# nixie_test_v3.net
KiCad netlist of a schematic drawn in EAGLE
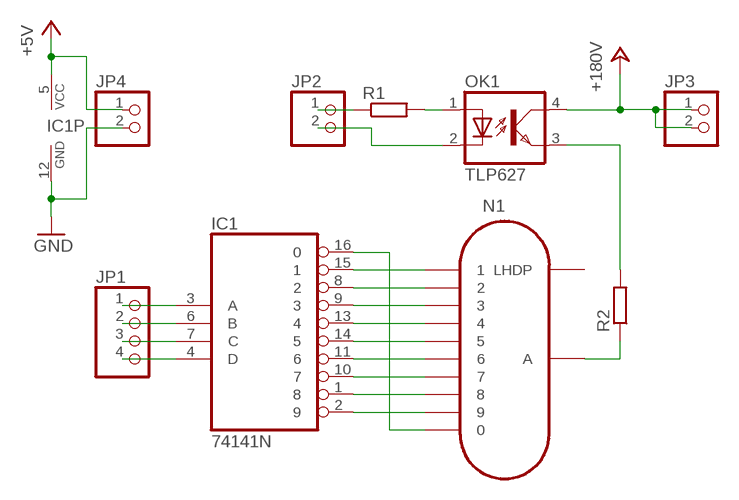
[diagram p0: schematic, sheet 1]

(export (version "E")
  (design (tool "Eeschema 10.0.6"))
  (components
    (comp (ref "IC1")
      (value "74141N")
      (footprint "eagle-import:DIL16")
      (libsource (lib "eagle-import") (part "74141N"))
    )
    (comp (ref "JP1")
      (value "PINHD-1X4")
      (footprint "eagle-import:1X04")
      (libsource (lib "eagle-import") (part "PINHD-1X4"))
    )
    (comp (ref "JP2")
      (value "PINHD-1X2")
      (footprint "eagle-import:1X02")
      (libsource (lib "eagle-import") (part "PINHD-1X2"))
    )
    (comp (ref "JP3")
      (value "PINHD-1X2")
      (footprint "eagle-import:1X02")
      (libsource (lib "eagle-import") (part "PINHD-1X2"))
    )
    (comp (ref "JP4")
      (value "PINHD-1X2")
      (footprint "eagle-import:1X02")
      (libsource (lib "eagle-import") (part "PINHD-1X2"))
    )
    (comp (ref "N1")
      (value "IN-12B")
      (footprint "eagle-import:IN-12")
      (libsource (lib "eagle-import") (part "IN-12B"))
    )
    (comp (ref "OK1")
      (value "TLP627")
      (footprint "eagle-import:4-SMD")
      (libsource (lib "eagle-import") (part "TLP627"))
    )
    (comp (ref "R1")
      (value "R-EU_R0805")
      (footprint "eagle-import:R0805")
      (libsource (lib "eagle-import") (part "R-EU_R0805"))
    )
    (comp (ref "R2")
      (value "R-EU_10")
      (footprint "eagle-import:0207_10")
      (libsource (lib "eagle-import") (part "R-EU_10"))
    )
  )
  (nets
    (net (code "1") (name "+5V") (class "Default")
      (node (ref "IC1") (pin "5") (pinfunction "VCC_5") (pintype "power_in"))
      (node (ref "JP4") (pin "1") (pinfunction "1_1") (pintype "passive"))
    )
    (net (code "2") (name "+180V") (class "Default")
      (node (ref "JP3") (pin "1") (pinfunction "1_1") (pintype "passive"))
      (node (ref "JP3") (pin "2") (pinfunction "2_2") (pintype "passive"))
      (node (ref "OK1") (pin "4") (pinfunction "COL_4") (pintype "passive"))
    )
    (net (code "3") (name "GND") (class "Default")
      (node (ref "IC1") (pin "12") (pinfunction "GND_12") (pintype "power_in"))
      (node (ref "JP4") (pin "2") (pinfunction "2_2") (pintype "passive"))
    )
    (net (code "4") (name "Net-(IC1A-0)") (class "Default")
      (node (ref "IC1") (pin "16") (pinfunction "0_16") (pintype "open_collector"))
      (node (ref "N1") (pin "0") (pinfunction "0_0") (pintype "bidirectional"))
    )
    (net (code "5") (name "Net-(IC1A-1)") (class "Default")
      (node (ref "IC1") (pin "15") (pinfunction "1_15") (pintype "open_collector"))
      (node (ref "N1") (pin "1") (pinfunction "1_1") (pintype "bidirectional"))
    )
    (net (code "6") (name "Net-(IC1A-2)") (class "Default")
      (node (ref "IC1") (pin "8") (pinfunction "2_8") (pintype "open_collector"))
      (node (ref "N1") (pin "2") (pinfunction "2_2") (pintype "bidirectional"))
    )
    (net (code "7") (name "Net-(IC1A-3)") (class "Default")
      (node (ref "IC1") (pin "9") (pinfunction "3_9") (pintype "open_collector"))
      (node (ref "N1") (pin "3") (pinfunction "3_3") (pintype "bidirectional"))
    )
    (net (code "8") (name "Net-(IC1A-4)") (class "Default")
      (node (ref "IC1") (pin "13") (pinfunction "4_13") (pintype "open_collector"))
      (node (ref "N1") (pin "4") (pinfunction "4_4") (pintype "bidirectional"))
    )
    (net (code "9") (name "Net-(IC1A-5)") (class "Default")
      (node (ref "IC1") (pin "14") (pinfunction "5_14") (pintype "open_collector"))
      (node (ref "N1") (pin "5") (pinfunction "5_5") (pintype "bidirectional"))
    )
    (net (code "10") (name "Net-(IC1A-6)") (class "Default")
      (node (ref "IC1") (pin "11") (pinfunction "6_11") (pintype "open_collector"))
      (node (ref "N1") (pin "6") (pinfunction "6_6") (pintype "bidirectional"))
    )
    (net (code "11") (name "Net-(IC1A-7)") (class "Default")
      (node (ref "IC1") (pin "10") (pinfunction "7_10") (pintype "open_collector"))
      (node (ref "N1") (pin "7") (pinfunction "7_7") (pintype "bidirectional"))
    )
    (net (code "12") (name "Net-(IC1A-8)") (class "Default")
      (node (ref "IC1") (pin "1") (pinfunction "8_1") (pintype "open_collector"))
      (node (ref "N1") (pin "8") (pinfunction "8_8") (pintype "bidirectional"))
    )
    (net (code "13") (name "Net-(IC1A-9)") (class "Default")
      (node (ref "IC1") (pin "2") (pinfunction "9_2") (pintype "open_collector"))
      (node (ref "N1") (pin "9") (pinfunction "9_9") (pintype "bidirectional"))
    )
    (net (code "14") (name "Net-(IC1A-A)") (class "Default")
      (node (ref "IC1") (pin "3") (pinfunction "A_3") (pintype "input"))
      (node (ref "JP1") (pin "1") (pinfunction "1_1") (pintype "passive"))
    )
    (net (code "15") (name "Net-(IC1A-B)") (class "Default")
      (node (ref "IC1") (pin "6") (pinfunction "B_6") (pintype "input"))
      (node (ref "JP1") (pin "2") (pinfunction "2_2") (pintype "passive"))
    )
    (net (code "16") (name "Net-(IC1A-C)") (class "Default")
      (node (ref "IC1") (pin "7") (pinfunction "C_7") (pintype "input"))
      (node (ref "JP1") (pin "3") (pinfunction "3_3") (pintype "passive"))
    )
    (net (code "17") (name "Net-(IC1A-D)") (class "Default")
      (node (ref "IC1") (pin "4") (pinfunction "D_4") (pintype "input"))
      (node (ref "JP1") (pin "4") (pinfunction "4_4") (pintype "passive"))
    )
    (net (code "18") (name "Net-(JP2-Pad1)") (class "Default")
      (node (ref "JP2") (pin "1") (pinfunction "1_1") (pintype "passive"))
      (node (ref "R1") (pin "1") (pinfunction "1_1") (pintype "passive"))
    )
    (net (code "19") (name "Net-(N1-PadA)") (class "Default")
      (node (ref "N1") (pin "A") (pinfunction "A_A") (pintype "bidirectional"))
      (node (ref "R2") (pin "1") (pinfunction "1_1") (pintype "passive"))
    )
    (net (code "20") (name "Net-(OK1-A)") (class "Default")
      (node (ref "OK1") (pin "1") (pinfunction "A_1") (pintype "passive"))
      (node (ref "R1") (pin "2") (pinfunction "2_2") (pintype "passive"))
    )
    (net (code "21") (name "Net-(OK1-C)") (class "Default")
      (node (ref "JP2") (pin "2") (pinfunction "2_2") (pintype "passive"))
      (node (ref "OK1") (pin "2") (pinfunction "C_2") (pintype "passive"))
    )
    (net (code "22") (name "Net-(OK1-EMIT)") (class "Default")
      (node (ref "OK1") (pin "3") (pinfunction "EMIT_3") (pintype "passive"))
      (node (ref "R2") (pin "2") (pinfunction "2_2") (pintype "passive"))
    )
    (net (code "23") (name "unconnected-(N1-PadLHDP)") (class "Default")
      (node (ref "N1") (pin "LHDP") (pinfunction "LHDP_LHDP") (pintype "bidirectional"))
    )
  )
)
